# power.net
KiCad netlist of a schematic drawn in Altium Designer
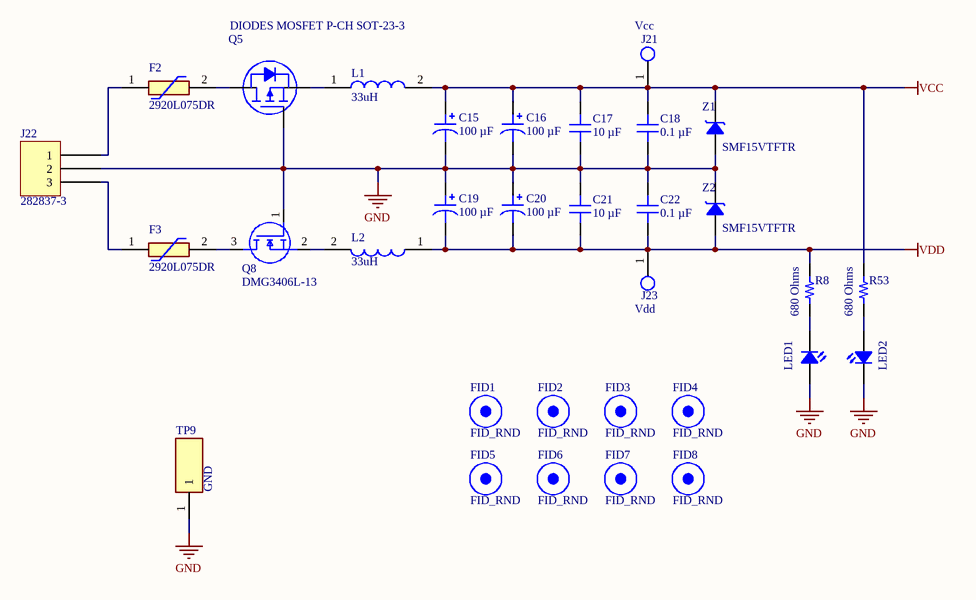
[diagram p0: power.SchDoc]

(export (version "E")
  (design (tool "Eeschema 10.0.6"))
  (components
    (comp (ref "C15")
      (value "100 µF")
      (footprint "CAP ALSMD 8.3MM H10.5MM")
      (description "CAP ALUM 100UF 20% 50V SMD")
      (fields (field (name "PART NUMBER") "50TZV100M8X10.5") (field (name "MANUFACTURER") "Rubycon"))
      (libsource (lib "Celestial Altium Library - altium_library") (part "Polarised Capacitor"))
    )
    (comp (ref "C16")
      (value "100 µF")
      (footprint "CAP ALSMD 8.3MM H10.5MM")
      (description "CAP ALUM 100UF 20% 50V SMD")
      (fields (field (name "PART NUMBER") "50TZV100M8X10.5") (field (name "MANUFACTURER") "Rubycon"))
      (libsource (lib "Celestial Altium Library - altium_library") (part "Polarised Capacitor"))
    )
    (comp (ref "C17")
      (value "10 µF")
      (footprint "CAP 1206_3216 - 0.8MM")
      (description "CAP CER 10UF 25V X7R 1206")
      (fields
        (field (name "PART NUMBER") "885012208069")
        (field (name "CAPACITANCE") "10 µF")
        (field (name "MANUFACTURER") "Würth Elektronik")
      )
      (libsource (lib "Celestial Altium Library - altium_library") (part "Capacitor"))
    )
    (comp (ref "C18")
      (value "0.1 µF")
      (footprint "CAP 1206_3216 - 0.8MM")
      (description "CAP CER 0.1UF 50V X7R 1206")
      (fields
        (field (name "PART NUMBER") "885012208087")
        (field (name "CAPACITANCE") "0.1 µF")
        (field (name "MANUFACTURER") "Würth Elektronik")
      )
      (libsource (lib "Celestial Altium Library - altium_library") (part "Capacitor"))
    )
    (comp (ref "C19")
      (value "100 µF")
      (footprint "CAP ALSMD 8.3MM H10.5MM")
      (description "CAP ALUM 100UF 20% 50V SMD")
      (fields (field (name "PART NUMBER") "50TZV100M8X10.5") (field (name "MANUFACTURER") "Rubycon"))
      (libsource (lib "Celestial Altium Library - altium_library") (part "Polarised Capacitor"))
    )
    (comp (ref "C20")
      (value "100 µF")
      (footprint "CAP ALSMD 8.3MM H10.5MM")
      (description "CAP ALUM 100UF 20% 50V SMD")
      (fields (field (name "PART NUMBER") "50TZV100M8X10.5") (field (name "MANUFACTURER") "Rubycon"))
      (libsource (lib "Celestial Altium Library - altium_library") (part "Polarised Capacitor"))
    )
    (comp (ref "C21")
      (value "10 µF")
      (footprint "CAP 1206_3216 - 0.8MM")
      (description "CAP CER 10UF 25V X7R 1206")
      (fields
        (field (name "PART NUMBER") "885012208069")
        (field (name "CAPACITANCE") "10 µF")
        (field (name "MANUFACTURER") "Würth Elektronik")
      )
      (libsource (lib "Celestial Altium Library - altium_library") (part "Capacitor"))
    )
    (comp (ref "C22")
      (value "0.1 µF")
      (footprint "CAP 1206_3216 - 0.8MM")
      (description "CAP CER 0.1UF 50V X7R 1206")
      (fields
        (field (name "PART NUMBER") "885012208087")
        (field (name "CAPACITANCE") "0.1 µF")
        (field (name "MANUFACTURER") "Würth Elektronik")
      )
      (libsource (lib "Celestial Altium Library - altium_library") (part "Capacitor"))
    )
    (comp (ref "F2")
      (value "2920L075DR")
      (footprint "za_koncar:2920L030DR")
      (description "Resettable Fuse")
      (fields (field (name "MOUSER PART NUMBER") "576-2920L075"))
      (libsource (lib "*") (part "2920L075DR"))
    )
    (comp (ref "F3")
      (value "2920L075DR")
      (footprint "za_koncar:2920L030DR")
      (description "Resettable Fuse")
      (fields (field (name "MOUSER PART NUMBER") "576-2920L075"))
      (libsource (lib "*") (part "2920L075DR"))
    )
    (comp (ref "FID1")
      (value "FID_RND")
      (footprint "FID_RND")
      (description "Fiducial, Round, D=4mm (inner D=1mm)")
      (fields (field (name "MANUFACTURER") "KONČAR"))
      (libsource (lib "za_koncar") (part "CMP-0288-0A"))
    )
    (comp (ref "FID2")
      (value "FID_RND")
      (footprint "FID_RND")
      (description "Fiducial, Round, D=4mm (inner D=1mm)")
      (fields (field (name "MANUFACTURER") "KONČAR"))
      (libsource (lib "za_koncar") (part "CMP-0288-0A"))
    )
    (comp (ref "FID3")
      (value "FID_RND")
      (footprint "FID_RND")
      (description "Fiducial, Round, D=4mm (inner D=1mm)")
      (fields (field (name "MANUFACTURER") "KONČAR"))
      (libsource (lib "za_koncar") (part "CMP-0288-0A"))
    )
    (comp (ref "FID4")
      (value "FID_RND")
      (footprint "FID_RND")
      (description "Fiducial, Round, D=4mm (inner D=1mm)")
      (fields (field (name "MANUFACTURER") "KONČAR"))
      (libsource (lib "za_koncar") (part "CMP-0288-0A"))
    )
    (comp (ref "FID5")
      (value "FID_RND")
      (footprint "FID_RND")
      (description "Fiducial, Round, D=4mm (inner D=1mm)")
      (fields (field (name "MANUFACTURER") "KONČAR"))
      (libsource (lib "za_koncar") (part "CMP-0288-0A"))
    )
    (comp (ref "FID6")
      (value "FID_RND")
      (footprint "FID_RND")
      (description "Fiducial, Round, D=4mm (inner D=1mm)")
      (fields (field (name "MANUFACTURER") "KONČAR"))
      (libsource (lib "za_koncar") (part "CMP-0288-0A"))
    )
    (comp (ref "FID7")
      (value "FID_RND")
      (footprint "FID_RND")
      (description "Fiducial, Round, D=4mm (inner D=1mm)")
      (fields (field (name "MANUFACTURER") "KONČAR"))
      (libsource (lib "za_koncar") (part "CMP-0288-0A"))
    )
    (comp (ref "FID8")
      (value "FID_RND")
      (footprint "FID_RND")
      (description "Fiducial, Round, D=4mm (inner D=1mm)")
      (fields (field (name "MANUFACTURER") "KONČAR"))
      (libsource (lib "za_koncar") (part "CMP-0288-0A"))
    )
    (comp (ref "J21")
      (value "Vcc")
      (footprint "FP-5001-MFG")
      (description "PC TEST POINT MINIATURE BLACK")
      (libsource (lib "za_koncar") (part "5001"))
    )
    (comp (ref "J22")
      (value "282837-3")
      (footprint "TE 282837-3")
      (description "TERM BLK 3P SIDE ENT 5.08MM PCB")
      (fields (field (name "MANUFACTURER") "TE Connectivity AMP Connectors") (field (name "VOLTAGE") "300 V"))
      (libsource (lib "Celestial Altium Library - altium_library") (part "3 Pin"))
    )
    (comp (ref "J23")
      (value "Vdd")
      (footprint "FP-5001-MFG")
      (description "PC TEST POINT MINIATURE BLACK")
      (libsource (lib "za_koncar") (part "5001"))
    )
    (comp (ref "L1")
      (value "33uH")
      (footprint "SamacSys:INDPM116102X400N")
      (description "Inductor")
      (fields
        (field (name "MANUFACTURER_PART_NUMBER") "AMRM00101040330MA1")
        (field (name "MOUSER PART NUMBER") "673-AMRM101040330MA1")
      )
      (libsource (lib "za_koncar") (part "AMRM00101040330MA1"))
    )
    (comp (ref "L2")
      (value "33uH")
      (footprint "SamacSys:INDPM116102X400N")
      (description "Inductor")
      (fields
        (field (name "MANUFACTURER_PART_NUMBER") "AMRM00101040330MA1")
        (field (name "MOUSER PART NUMBER") "673-AMRM101040330MA1")
      )
      (libsource (lib "za_koncar") (part "AMRM00101040330MA1"))
    )
    (comp (ref "LED1")
      (value "LTST-C191KRKT")
      (footprint "za_koncar:LEDC1608X55N")
      (description "LED")
      (fields (field (name "MOUSER PART NUMBER") "859-LTST-C191KRKT"))
      (libsource (lib "za_koncar") (part "LTST-C191KRKT"))
    )
    (comp (ref "LED2")
      (value "LTST-C191KRKT")
      (footprint "za_koncar:LEDC1608X55N")
      (description "LED")
      (fields (field (name "MOUSER PART NUMBER") "859-LTST-C191KRKT"))
      (libsource (lib "za_koncar") (part "LTST-C191KRKT"))
    )
    (comp (ref "Q5")
      (value "DIODES MOSFET P-CH SOT-23-3")
      (footprint "DIODES SOT-23-3")
      (description "MOSFET P-CH 30V 2.5A SOT23")
      (fields (field (name "PART NUMBER") "DMP3125L-7") (field (name "MANUFACTURER") "Diodes Incorporated"))
      (libsource (lib "Celestial Altium Library - altium_library") (part "DIODES MOSFET P-CH SOT-23-3"))
    )
    (comp (ref "Q8")
      (value "DMG3406L-13")
      (footprint "SOT96P240X110-3N")
      (description "MOSFET (N-Channel)")
      (fields (field (name "MOUSER PART NUMBER") "621-DMG3406L-13"))
      (libsource (lib "za_koncar") (part "DMG3406L-13"))
    )
    (comp (ref "R8")
      (value "680 Ohms")
      (footprint "YAGEO RES 1206_3216")
      (description "RES SMD 680 OHM 1% 1/4W 1206")
      (fields (field (name "PART NUMBER") "RT1206FRE07680RL") (field (name "MANUFACTURER") "Yageo"))
      (libsource (lib "Celestial Altium Library - altium_library") (part "Resistor"))
    )
    (comp (ref "R53")
      (value "680 Ohms")
      (footprint "YAGEO RES 1206_3216")
      (description "RES SMD 680 OHM 1% 1/4W 1206")
      (fields (field (name "PART NUMBER") "RT1206FRE07680RL") (field (name "MANUFACTURER") "Yageo"))
      (libsource (lib "Celestial Altium Library - altium_library") (part "Resistor"))
    )
    (comp (ref "TP9")
      (value "GND")
      (footprint "za_koncar:S175146R")
      (description "Test Point")
      (fields
        (field (name "MANUFACTURER_PART_NUMBER") "S1751-46R")
        (field (name "MOUSER PART NUMBER") "855-S1751-46R")
      )
      (libsource (lib "za_koncar") (part "S1751-46R"))
    )
    (comp (ref "Z1")
      (value "SMF15VTFTR")
      (footprint "SMF15VTFTR")
      (description "Zener Diode")
      (fields (field (name "MOUSER PART NUMBER") "755-SMF15VTFTR"))
      (libsource (lib "za_koncar") (part "SMF15VTFTR"))
    )
    (comp (ref "Z2")
      (value "SMF15VTFTR")
      (footprint "SMF15VTFTR")
      (description "Zener Diode")
      (fields (field (name "MOUSER PART NUMBER") "755-SMF15VTFTR"))
      (libsource (lib "za_koncar") (part "SMF15VTFTR"))
    )
  )
  (nets
    (net (code "1") (name "GND") (class "Default")
      (node (ref "C15") (pin "2") (pinfunction "2_2") (pintype "passive"))
      (node (ref "C16") (pin "2") (pinfunction "2_2") (pintype "passive"))
      (node (ref "C17") (pin "1") (pinfunction "1_1") (pintype "passive"))
      (node (ref "C18") (pin "1") (pinfunction "1_1") (pintype "passive"))
      (node (ref "C19") (pin "1") (pinfunction "1_1") (pintype "passive"))
      (node (ref "C20") (pin "1") (pinfunction "1_1") (pintype "passive"))
      (node (ref "C21") (pin "2") (pinfunction "2_2") (pintype "passive"))
      (node (ref "C22") (pin "2") (pinfunction "2_2") (pintype "passive"))
      (node (ref "J22") (pin "2") (pinfunction "2_2") (pintype "passive"))
      (node (ref "LED1") (pin "2") (pinfunction "A_2") (pintype "passive"))
      (node (ref "LED2") (pin "1") (pinfunction "K_1") (pintype "passive"))
      (node (ref "Q5") (pin "1") (pinfunction "G_1") (pintype "passive"))
      (node (ref "Q8") (pin "1") (pinfunction "G_1") (pintype "passive"))
      (node (ref "TP9") (pin "1") (pinfunction "1_1") (pintype "passive"))
      (node (ref "Z1") (pin "2") (pinfunction "2_2") (pintype "passive"))
      (node (ref "Z2") (pin "1") (pinfunction "1_1") (pintype "passive"))
    )
    (net (code "2") (name "Net-(F2-Pad1)") (class "Default")
      (node (ref "F2") (pin "1") (pinfunction "1_1") (pintype "passive"))
      (node (ref "J22") (pin "1") (pinfunction "1_1") (pintype "passive"))
    )
    (net (code "3") (name "Net-(F3-Pad1)") (class "Default")
      (node (ref "F3") (pin "1") (pinfunction "1_1") (pintype "passive"))
      (node (ref "J22") (pin "3") (pinfunction "3_3") (pintype "passive"))
    )
    (net (code "4") (name "Net-(LED1-K)") (class "Default")
      (node (ref "LED1") (pin "1") (pinfunction "K_1") (pintype "passive"))
      (node (ref "R8") (pin "1") (pinfunction "1_1") (pintype "passive"))
    )
    (net (code "5") (name "Net-(LED2-A)") (class "Default")
      (node (ref "LED2") (pin "2") (pinfunction "A_2") (pintype "passive"))
      (node (ref "R53") (pin "1") (pinfunction "1_1") (pintype "passive"))
    )
    (net (code "6") (name "Net-(Q5-D)") (class "Default")
      (node (ref "F2") (pin "2") (pinfunction "2_2") (pintype "passive"))
      (node (ref "Q5") (pin "3") (pinfunction "D_3") (pintype "passive"))
    )
    (net (code "7") (name "Net-(Q5-S)") (class "Default")
      (node (ref "L1") (pin "1") (pinfunction "1_1") (pintype "passive"))
      (node (ref "Q5") (pin "2") (pinfunction "S_2") (pintype "passive"))
    )
    (net (code "8") (name "Net-(Q8-D)") (class "Default")
      (node (ref "F3") (pin "2") (pinfunction "2_2") (pintype "passive"))
      (node (ref "Q8") (pin "3") (pinfunction "D_3") (pintype "passive"))
    )
    (net (code "9") (name "Net-(Q8-S)") (class "Default")
      (node (ref "L2") (pin "2") (pinfunction "2_2") (pintype "passive"))
      (node (ref "Q8") (pin "2") (pinfunction "S_2") (pintype "passive"))
    )
    (net (code "10") (name "VCC") (class "Default")
      (node (ref "C15") (pin "1") (pinfunction "1_1") (pintype "passive"))
      (node (ref "C16") (pin "1") (pinfunction "1_1") (pintype "passive"))
      (node (ref "C17") (pin "2") (pinfunction "2_2") (pintype "passive"))
      (node (ref "C18") (pin "2") (pinfunction "2_2") (pintype "passive"))
      (node (ref "J21") (pin "1") (pinfunction "1_1") (pintype "passive"))
      (node (ref "L1") (pin "2") (pinfunction "2_2") (pintype "passive"))
      (node (ref "R53") (pin "2") (pinfunction "2_2") (pintype "passive"))
      (node (ref "Z1") (pin "1") (pinfunction "1_1") (pintype "passive"))
    )
    (net (code "11") (name "VDD") (class "Default")
      (node (ref "C19") (pin "2") (pinfunction "2_2") (pintype "passive"))
      (node (ref "C20") (pin "2") (pinfunction "2_2") (pintype "passive"))
      (node (ref "C21") (pin "1") (pinfunction "1_1") (pintype "passive"))
      (node (ref "C22") (pin "1") (pinfunction "1_1") (pintype "passive"))
      (node (ref "J23") (pin "1") (pinfunction "1_1") (pintype "passive"))
      (node (ref "L2") (pin "1") (pinfunction "1_1") (pintype "passive"))
      (node (ref "R8") (pin "2") (pinfunction "2_2") (pintype "passive"))
      (node (ref "Z2") (pin "2") (pinfunction "2_2") (pintype "passive"))
    )
  )
)
